# GD_Tcontroller_MCU.net
KiCad netlist of a schematic drawn in Altium Designer
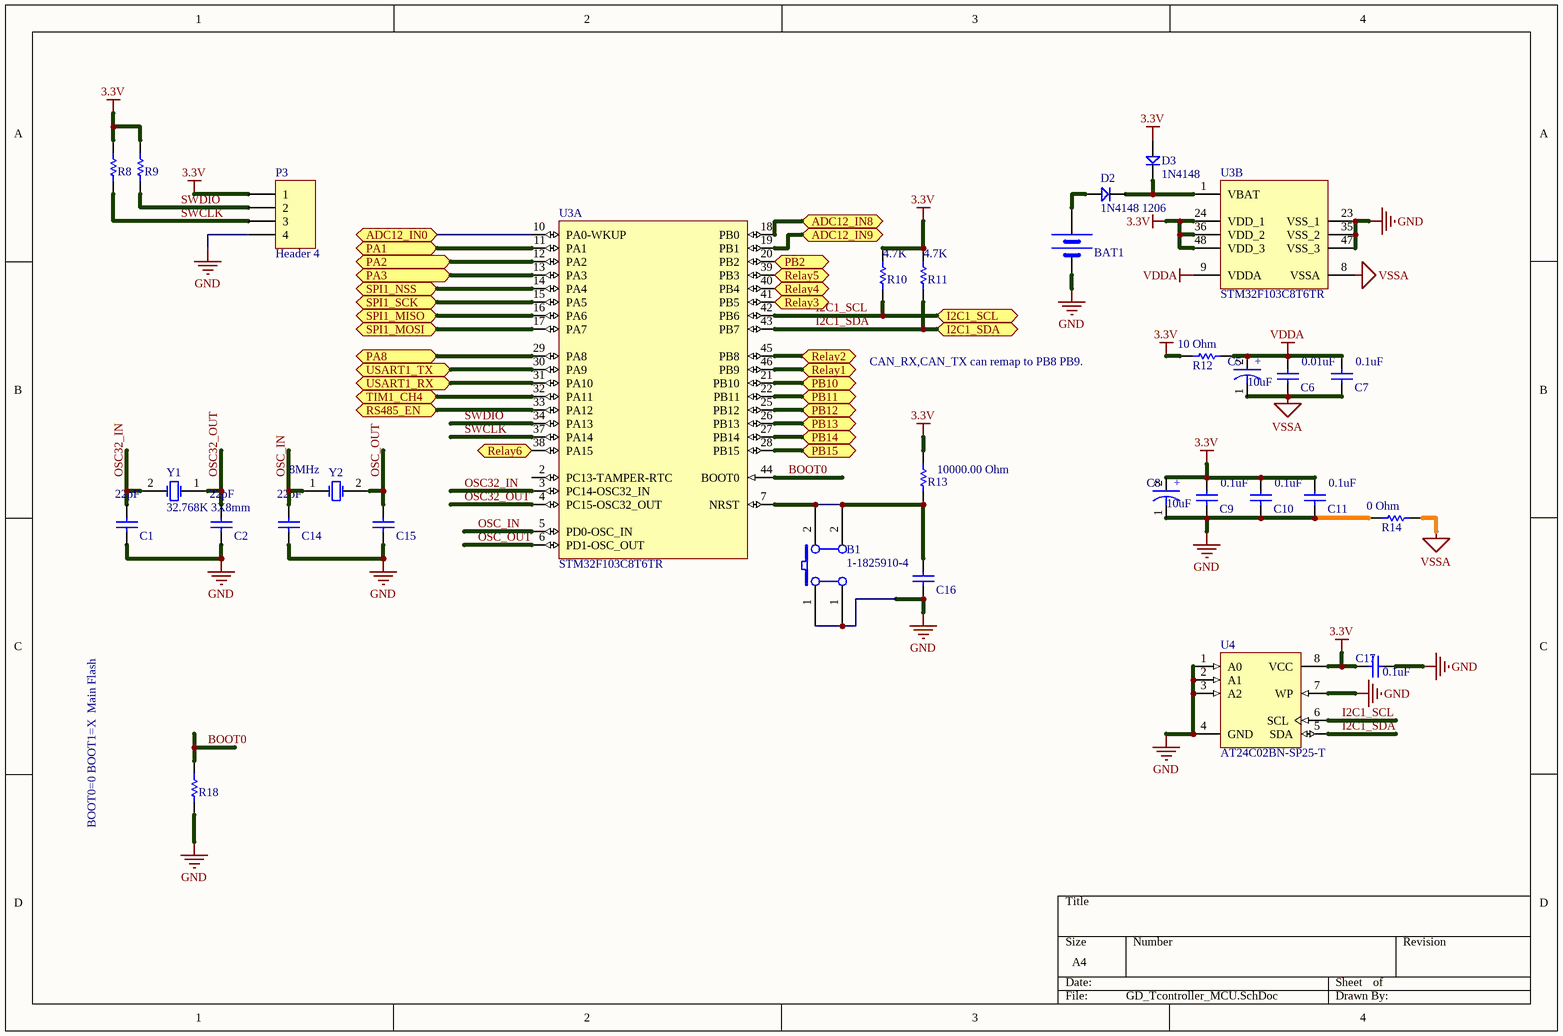
[diagram p0: GD_Tcontroller_MCU.SchDoc]

(export (version "E")
  (design (tool "Eeschema 10.0.6"))
  (components
    (comp (ref "B1")
      (value "1-1825910-4")
      (footprint "AN6_3P6_5")
      (description "Button ON/OFF，6.3X6.3X9.5MM,DIP-2")
      (fields (field (name "MANUFACTURER") "Tyco Electronics") (field (name "Comment") "SW PUSHBUTTON"))
      (libsource (lib "enlogic") (part "SW PUSHBUTTON"))
    )
    (comp (ref "BAT1")
      (value "CR1220 Sockect SMD")
      (footprint "BATM")
      (libsource (lib "战舰STM32开发板底板封装库") (part "BAT"))
    )
    (comp (ref "C1")
      (value "22pF")
      (footprint "C0805")
      (description "CAP 22pF 50V ±1% 0805 (2012 Metric) Thickness 0.75mm SMD")
      (fields (field (name "TOLERANCE") "±1%") (field (name "Comment") "CAP 22pF 50V 0805(2012)"))
      (libsource (lib "Altium Content Vault") (part "CMP-1036-01234-1"))
    )
    (comp (ref "C2")
      (value "22pF")
      (footprint "C0805")
      (description "CAP 22pF 50V ±1% 0805 (2012 Metric) Thickness 0.75mm SMD")
      (fields (field (name "TOLERANCE") "±1%") (field (name "Comment") "CAP 22pF 50V 0805(2012)"))
      (libsource (lib "Altium Content Vault") (part "CMP-1036-01234-1"))
    )
    (comp (ref "C5")
      (value "10uF")
      (footprint "TAN3216")
      (description "TAN 10uF 20% 10V 3216")
      (fields (field (name "MANUFACTURER") "AVX") (field (name "Comment") "CAPACITOR"))
      (libsource (lib "enlogic") (part "CAPACITOR"))
    )
    (comp (ref "C6")
      (value "0.01uF")
      (footprint "C0805")
      (description "CAP 0.1uF 50V ±20% 0805 (2012 Metric) Thickness 1mm SMD")
      (fields (field (name "TOLERANCE") "20%") (field (name "Comment") "CAP 0.01uF 50V 0805(2012)"))
      (libsource (lib "Altium Content Vault") (part "CMP-1036-00070-1"))
    )
    (comp (ref "C7")
      (value "0.1uF")
      (footprint "C0805")
      (description "CAP 0.1uF 50V ±20% 0805 (2012 Metric) Thickness 1mm SMD")
      (fields (field (name "TOLERANCE") "20%") (field (name "Comment") "CAP 0.1uF 50V 0805(2012)"))
      (libsource (lib "Altium Content Vault") (part "CMP-1036-00070-1"))
    )
    (comp (ref "C8")
      (value "10uF")
      (footprint "TAN3216")
      (description "TAN 10uF 20% 10V 3216")
      (fields (field (name "MANUFACTURER") "AVX") (field (name "Comment") "CAPACITOR"))
      (libsource (lib "enlogic") (part "CAPACITOR"))
    )
    (comp (ref "C9")
      (value "0.1uF")
      (footprint "C0805")
      (description "CAP 0.1uF 50V ±20% 0805 (2012 Metric) Thickness 1mm SMD")
      (fields (field (name "TOLERANCE") "20%") (field (name "Comment") "CAP 0.1uF 50V 0805(2012)"))
      (libsource (lib "Altium Content Vault") (part "CMP-1036-00070-1"))
    )
    (comp (ref "C10")
      (value "0.1uF")
      (footprint "C0805")
      (description "CAP 0.1uF 50V ±20% 0805 (2012 Metric) Thickness 1mm SMD")
      (fields (field (name "TOLERANCE") "20%") (field (name "Comment") "CAP 0.1uF 50V 0805(2012)"))
      (libsource (lib "Altium Content Vault") (part "CMP-1036-00070-1"))
    )
    (comp (ref "C11")
      (value "0.1uF")
      (footprint "C0805")
      (description "CAP 0.1uF 50V ±20% 0805 (2012 Metric) Thickness 1mm SMD")
      (fields (field (name "TOLERANCE") "20%") (field (name "Comment") "CAP 0.1uF 50V 0805(2012)"))
      (libsource (lib "Altium Content Vault") (part "CMP-1036-00070-1"))
    )
    (comp (ref "C14")
      (value "22pF")
      (footprint "C0805")
      (description "CAP 22pF 50V ±1% 0805 (2012 Metric) Thickness 0.75mm SMD")
      (fields (field (name "TOLERANCE") "±1%") (field (name "Comment") "CAP 22pF 50V 0805(2012)"))
      (libsource (lib "Altium Content Vault") (part "CMP-1036-01234-1"))
    )
    (comp (ref "C15")
      (value "CAP 22pF 50V 0805(2012)")
      (footprint "C0805")
      (description "CAP 22pF 50V ±1% 0805 (2012 Metric) Thickness 0.75mm SMD")
      (fields (field (name "TOLERANCE") "±1%"))
      (libsource (lib "Altium Content Vault") (part "CAP"))
    )
    (comp (ref "C16")
      (value "CAP 0.1uF 50V 0805(2012)")
      (footprint "C0805")
      (description "CAP 0.1uF 50V ±20% 0805 (2012 Metric) Thickness 1mm SMD")
      (fields (field (name "TOLERANCE") "20%"))
      (libsource (lib "Altium Content Vault") (part "CMP-1036-00070-1"))
    )
    (comp (ref "C17")
      (value "0.1uF")
      (footprint "C0805")
      (description "CAP 0.1uF 50V ±20% 0805 (2012 Metric) Thickness 1mm SMD")
      (fields (field (name "TOLERANCE") "20%") (field (name "Comment") "CAP 0.1uF 50V 0805(2012)"))
      (libsource (lib "Altium Content Vault") (part "CMP-1036-00070-1"))
    )
    (comp (ref "D2")
      (value "1N4148 1206")
      (footprint "DIODE_SOP")
      (description "1N4148")
      (libsource (lib "MiniSTM32 V3.0封装库") (part "D"))
    )
    (comp (ref "D3")
      (value "1N4148")
      (footprint "DIODE_SOP")
      (libsource (lib "MiniSTM32 V3.0封装库") (part "D"))
    )
    (comp (ref "P3")
      (value "Header 4")
      (footprint "HDR1X4")
      (description "Header, 4-Pin")
      (fields (field (name "PUBLISHER") "Altium Limited"))
      (libsource (lib "Miscellaneous Connectors") (part "Header 4"))
    )
    (comp (ref "R8")
      (value "10K 5% 0805(2012)")
      (footprint "R0805")
      (description "10K 0.125W 5% 0805 (2012 Metric)  SMD")
      (fields (field (name "POWER") "0.125 W") (field (name "TOLERANCE") "5 %"))
      (libsource (lib "Altium Content Vault") (part "RES"))
    )
    (comp (ref "R9")
      (value "10K 5% 0805(2012)")
      (footprint "R0805")
      (description "10K 0.125W 5% 0805 (2012 Metric)  SMD")
      (fields (field (name "POWER") "0.125 W") (field (name "TOLERANCE") "5 %"))
      (libsource (lib "Altium Content Vault") (part "RES"))
    )
    (comp (ref "R10")
      (value "4.7K")
      (footprint "R0805")
      (description "4.7K 0.125W 5% 0805 (2012 Metric)  SMD")
      (fields (field (name "POWER") "0.125 W") (field (name "TOLERANCE") "5 %"))
      (libsource (lib "Altium Content Vault") (part "CMP-1013-00098-1"))
    )
    (comp (ref "R11")
      (value "4.7K")
      (footprint "R0805")
      (description "4.7K 0.125W 5% 0805 (2012 Metric)  SMD")
      (fields (field (name "POWER") "0.125 W") (field (name "TOLERANCE") "5 %"))
      (libsource (lib "Altium Content Vault") (part "CMP-1013-00098-1"))
    )
    (comp (ref "R12")
      (value "10 Ohm")
      (footprint "R0805")
      (description "10Ohm 0.125W 5% 0805 (2012 Metric)  SMD")
      (fields (field (name "POWER") "0.125 W") (field (name "TOLERANCE") "5 %"))
      (libsource (lib "Altium Content Vault") (part "CMP-1013-00098-1"))
    )
    (comp (ref "R13")
      (value "10000.00 Ohm")
      (footprint "R0805")
      (description "10K 0.125W 5% 0805 (2012 Metric)  SMD")
      (fields (field (name "POWER") "0.125 W") (field (name "TOLERANCE") "5 %"))
      (libsource (lib "Altium Content Vault") (part "CMP-1013-00098-1"))
    )
    (comp (ref "R14")
      (value "0 Ohm")
      (footprint "R0805")
      (description "10Ohm 0.125W 5% 0805 (2012 Metric)  SMD")
      (fields (field (name "POWER") "0.125 W") (field (name "TOLERANCE") "5 %"))
      (libsource (lib "Altium Content Vault") (part "CMP-1013-00098-1"))
    )
    (comp (ref "R18")
      (value "10K 5% 0805(2012)")
      (footprint "R0805")
      (description "10K 0.125W 5% 0805 (2012 Metric)  SMD")
      (fields (field (name "POWER") "0.125 W") (field (name "TOLERANCE") "5 %"))
      (libsource (lib "Altium Content Vault") (part "RES"))
    )
    (comp (ref "U3")
      (value "STM32F103C8T6TR")
      (footprint "STM-LQFP48_L")
      (libsource (lib "Altium Content Vault") (part "CMP-0237-00216-3"))
    )
    (comp (ref "U4")
      (value "AT24C02BN-SP25-T")
      (footprint "8S1_L")
      (libsource (lib "Altium Content Vault") (part "CMP-0152-00023-1"))
    )
    (comp (ref "Y1")
      (value "32.768K 3X8mm")
      (footprint "XTAL32")
      (description "32.768K 3mmX8mm")
      (fields (field (name "PUBLISHER") "Altium Limited"))
      (libsource (lib "战舰STM32开发板底板封装库") (part "XTAL_1"))
    )
    (comp (ref "Y2")
      (value "8MHz")
      (footprint "XTAL_US")
      (description "Crystal Oscillator")
      (fields (field (name "PUBLISHER") "Altium Limited"))
      (libsource (lib "战舰STM32开发板底板封装库") (part "XTAL"))
    )
  )
  (nets
    (net (code "1") (name "/ADC12_IN0") (class "Default")
      (node (ref "U3") (pin "10") (pinfunction "PA0-WKUP_10") (pintype "bidirectional"))
    )
    (net (code "2") (name "/ADC12_IN8") (class "Default")
      (node (ref "U3") (pin "18") (pinfunction "PB0_18") (pintype "bidirectional"))
    )
    (net (code "3") (name "/ADC12_IN9") (class "Default")
      (node (ref "U3") (pin "19") (pinfunction "PB1_19") (pintype "bidirectional"))
    )
    (net (code "4") (name "/BOOT0") (class "Default")
      (node (ref "R18") (pin "1") (pinfunction "1_1") (pintype "passive"))
      (node (ref "U3") (pin "44") (pinfunction "BOOT0_44") (pintype "input"))
    )
    (net (code "5") (name "/I2C1_SCL") (class "Default")
      (node (ref "R10") (pin "2") (pinfunction "2_2") (pintype "passive"))
      (node (ref "U3") (pin "42") (pinfunction "PB6_42") (pintype "bidirectional"))
      (node (ref "U4") (pin "6") (pinfunction "SCL_6") (pintype "input"))
    )
    (net (code "6") (name "/I2C1_SDA") (class "Default")
      (node (ref "R11") (pin "2") (pinfunction "2_2") (pintype "passive"))
      (node (ref "U3") (pin "43") (pinfunction "PB7_43") (pintype "bidirectional"))
      (node (ref "U4") (pin "5") (pinfunction "SDA_5") (pintype "bidirectional"))
    )
    (net (code "7") (name "/OSC32_IN") (class "Default")
      (node (ref "C1") (pin "2") (pinfunction "2_2") (pintype "passive"))
      (node (ref "U3") (pin "3") (pinfunction "PC14-OSC32_IN_3") (pintype "bidirectional"))
      (node (ref "Y1") (pin "2") (pinfunction "OSC2_2") (pintype "passive"))
    )
    (net (code "8") (name "/OSC32_OUT") (class "Default")
      (node (ref "C2") (pin "2") (pinfunction "2_2") (pintype "passive"))
      (node (ref "U3") (pin "4") (pinfunction "PC15-OSC32_OUT_4") (pintype "bidirectional"))
      (node (ref "Y1") (pin "1") (pinfunction "OSC1_1") (pintype "passive"))
    )
    (net (code "9") (name "/OSC_IN") (class "Default")
      (node (ref "C14") (pin "2") (pinfunction "2_2") (pintype "passive"))
      (node (ref "U3") (pin "5") (pinfunction "PD0-OSC_IN_5") (pintype "bidirectional"))
      (node (ref "Y2") (pin "1") (pinfunction "OSC1_1") (pintype "passive"))
    )
    (net (code "10") (name "/OSC_OUT") (class "Default")
      (node (ref "C15") (pin "2") (pinfunction "2_2") (pintype "passive"))
      (node (ref "U3") (pin "6") (pinfunction "PD1-OSC_OUT_6") (pintype "bidirectional"))
      (node (ref "Y2") (pin "2") (pinfunction "OSC2_2") (pintype "passive"))
    )
    (net (code "11") (name "/PA1") (class "Default")
      (node (ref "U3") (pin "11") (pinfunction "PA1_11") (pintype "bidirectional"))
    )
    (net (code "12") (name "/PA2") (class "Default")
      (node (ref "U3") (pin "12") (pinfunction "PA2_12") (pintype "bidirectional"))
    )
    (net (code "13") (name "/PA3") (class "Default")
      (node (ref "U3") (pin "13") (pinfunction "PA3_13") (pintype "bidirectional"))
    )
    (net (code "14") (name "/PA8") (class "Default")
      (node (ref "U3") (pin "29") (pinfunction "PA8_29") (pintype "bidirectional"))
    )
    (net (code "15") (name "/PB2") (class "Default")
      (node (ref "U3") (pin "20") (pinfunction "PB2_20") (pintype "bidirectional"))
    )
    (net (code "16") (name "/PB10") (class "Default")
      (node (ref "U3") (pin "21") (pinfunction "PB10_21") (pintype "bidirectional"))
    )
    (net (code "17") (name "/PB11") (class "Default")
      (node (ref "U3") (pin "22") (pinfunction "PB11_22") (pintype "bidirectional"))
    )
    (net (code "18") (name "/PB12") (class "Default")
      (node (ref "U3") (pin "25") (pinfunction "PB12_25") (pintype "bidirectional"))
    )
    (net (code "19") (name "/PB13") (class "Default")
      (node (ref "U3") (pin "26") (pinfunction "PB13_26") (pintype "bidirectional"))
    )
    (net (code "20") (name "/PB14") (class "Default")
      (node (ref "U3") (pin "27") (pinfunction "PB14_27") (pintype "bidirectional"))
    )
    (net (code "21") (name "/PB15") (class "Default")
      (node (ref "U3") (pin "28") (pinfunction "PB15_28") (pintype "bidirectional"))
    )
    (net (code "22") (name "/RS485_EN") (class "Default")
      (node (ref "U3") (pin "33") (pinfunction "PA12_33") (pintype "bidirectional"))
    )
    (net (code "23") (name "/Relay1") (class "Default")
      (node (ref "U3") (pin "46") (pinfunction "PB9_46") (pintype "bidirectional"))
    )
    (net (code "24") (name "/Relay2") (class "Default")
      (node (ref "U3") (pin "45") (pinfunction "PB8_45") (pintype "bidirectional"))
    )
    (net (code "25") (name "/Relay3") (class "Default")
      (node (ref "U3") (pin "41") (pinfunction "PB5_41") (pintype "bidirectional"))
    )
    (net (code "26") (name "/Relay4") (class "Default")
      (node (ref "U3") (pin "40") (pinfunction "PB4_40") (pintype "bidirectional"))
    )
    (net (code "27") (name "/Relay5") (class "Default")
      (node (ref "U3") (pin "39") (pinfunction "PB3_39") (pintype "bidirectional"))
    )
    (net (code "28") (name "/Relay6") (class "Default")
      (node (ref "U3") (pin "38") (pinfunction "PA15_38") (pintype "bidirectional"))
    )
    (net (code "29") (name "/SPI1_MISO") (class "Default")
      (node (ref "U3") (pin "16") (pinfunction "PA6_16") (pintype "bidirectional"))
    )
    (net (code "30") (name "/SPI1_MOSI") (class "Default")
      (node (ref "U3") (pin "17") (pinfunction "PA7_17") (pintype "bidirectional"))
    )
    (net (code "31") (name "/SPI1_NSS") (class "Default")
      (node (ref "U3") (pin "14") (pinfunction "PA4_14") (pintype "bidirectional"))
    )
    (net (code "32") (name "/SPI1_SCK") (class "Default")
      (node (ref "U3") (pin "15") (pinfunction "PA5_15") (pintype "bidirectional"))
    )
    (net (code "33") (name "/SWCLK") (class "Default")
      (node (ref "P3") (pin "3") (pinfunction "3_3") (pintype "passive"))
      (node (ref "R8") (pin "2") (pinfunction "2_2") (pintype "passive"))
      (node (ref "U3") (pin "37") (pinfunction "PA14_37") (pintype "bidirectional"))
    )
    (net (code "34") (name "/SWDIO") (class "Default")
      (node (ref "P3") (pin "2") (pinfunction "2_2") (pintype "passive"))
      (node (ref "R9") (pin "2") (pinfunction "2_2") (pintype "passive"))
      (node (ref "U3") (pin "34") (pinfunction "PA13_34") (pintype "bidirectional"))
    )
    (net (code "35") (name "/TIM1_CH4") (class "Default")
      (node (ref "U3") (pin "32") (pinfunction "PA11_32") (pintype "bidirectional"))
    )
    (net (code "36") (name "/USART1_RX") (class "Default")
      (node (ref "U3") (pin "31") (pinfunction "PA10_31") (pintype "bidirectional"))
    )
    (net (code "37") (name "/USART1_TX") (class "Default")
      (node (ref "U3") (pin "30") (pinfunction "PA9_30") (pintype "bidirectional"))
    )
    (net (code "38") (name "3.3V") (class "Default")
      (node (ref "C10") (pin "2") (pinfunction "2_2") (pintype "passive"))
      (node (ref "C11") (pin "2") (pinfunction "2_2") (pintype "passive"))
      (node (ref "C17") (pin "2") (pinfunction "2_2") (pintype "passive"))
      (node (ref "C8") (pin "2") (pinfunction "2_2") (pintype "passive"))
      (node (ref "C9") (pin "2") (pinfunction "2_2") (pintype "passive"))
      (node (ref "D3") (pin "1") (pintype "passive"))
      (node (ref "P3") (pin "1") (pinfunction "1_1") (pintype "passive"))
      (node (ref "R10") (pin "1") (pinfunction "1_1") (pintype "passive"))
      (node (ref "R11") (pin "1") (pinfunction "1_1") (pintype "passive"))
      (node (ref "R12") (pin "1") (pinfunction "1_1") (pintype "passive"))
      (node (ref "R13") (pin "1") (pinfunction "1_1") (pintype "passive"))
      (node (ref "R8") (pin "1") (pinfunction "1_1") (pintype "passive"))
      (node (ref "R9") (pin "1") (pinfunction "1_1") (pintype "passive"))
      (node (ref "U3") (pin "24") (pinfunction "VDD_1_24") (pintype "power_in"))
      (node (ref "U3") (pin "36") (pinfunction "VDD_2_36") (pintype "power_in"))
      (node (ref "U3") (pin "48") (pinfunction "VDD_3_48") (pintype "power_in"))
      (node (ref "U4") (pin "8") (pinfunction "VCC_8") (pintype "power_in"))
    )
    (net (code "39") (name "GND") (class "Default")
      (node (ref "B1") (pin "1") (pinfunction "A0_1") (pintype "passive"))
      (node (ref "BAT1") (pin "2") (pinfunction "GND_2") (pintype "passive"))
      (node (ref "C1") (pin "1") (pinfunction "1_1") (pintype "passive"))
      (node (ref "C10") (pin "1") (pinfunction "1_1") (pintype "passive"))
      (node (ref "C11") (pin "1") (pinfunction "1_1") (pintype "passive"))
      (node (ref "C14") (pin "1") (pinfunction "1_1") (pintype "passive"))
      (node (ref "C15") (pin "1") (pinfunction "1_1") (pintype "passive"))
      (node (ref "C16") (pin "1") (pinfunction "1_1") (pintype "passive"))
      (node (ref "C17") (pin "1") (pinfunction "1_1") (pintype "passive"))
      (node (ref "C2") (pin "1") (pinfunction "1_1") (pintype "passive"))
      (node (ref "C8") (pin "1") (pinfunction "1_1") (pintype "passive"))
      (node (ref "C9") (pin "1") (pinfunction "1_1") (pintype "passive"))
      (node (ref "P3") (pin "4") (pinfunction "4_4") (pintype "passive"))
      (node (ref "R14") (pin "1") (pinfunction "1_1") (pintype "passive"))
      (node (ref "R18") (pin "2") (pinfunction "2_2") (pintype "passive"))
      (node (ref "U3") (pin "23") (pinfunction "VSS_1_23") (pintype "power_in"))
      (node (ref "U3") (pin "35") (pinfunction "VSS_2_35") (pintype "power_in"))
      (node (ref "U3") (pin "47") (pinfunction "VSS_3_47") (pintype "power_in"))
      (node (ref "U4") (pin "1") (pinfunction "A0_1") (pintype "input"))
      (node (ref "U4") (pin "2") (pinfunction "A1_2") (pintype "input"))
      (node (ref "U4") (pin "3") (pinfunction "A2_3") (pintype "input"))
      (node (ref "U4") (pin "4") (pinfunction "GND_4") (pintype "power_in"))
      (node (ref "U4") (pin "7") (pinfunction "WP_7") (pintype "input"))
    )
    (net (code "40") (name "Net-(B1-B0)") (class "Default")
      (node (ref "B1") (pin "2") (pinfunction "B0_2") (pintype "passive"))
      (node (ref "C16") (pin "2") (pinfunction "2_2") (pintype "passive"))
      (node (ref "R13") (pin "2") (pinfunction "2_2") (pintype "passive"))
      (node (ref "U3") (pin "7") (pinfunction "NRST_7") (pintype "bidirectional"))
    )
    (net (code "41") (name "Net-(BAT1-VCC)") (class "Default")
      (node (ref "BAT1") (pin "1") (pinfunction "VCC_1") (pintype "passive"))
      (node (ref "D2") (pin "1") (pintype "passive"))
    )
    (net (code "42") (name "Net-(U3B-VBAT)") (class "Default")
      (node (ref "D2") (pin "2") (pintype "passive"))
      (node (ref "D3") (pin "2") (pintype "passive"))
      (node (ref "U3") (pin "1") (pinfunction "VBAT_1") (pintype "power_in"))
    )
    (net (code "43") (name "VDDA") (class "Default")
      (node (ref "C5") (pin "2") (pinfunction "2_2") (pintype "passive"))
      (node (ref "C6") (pin "2") (pinfunction "2_2") (pintype "passive"))
      (node (ref "C7") (pin "2") (pinfunction "2_2") (pintype "passive"))
      (node (ref "R12") (pin "2") (pinfunction "2_2") (pintype "passive"))
      (node (ref "U3") (pin "9") (pinfunction "VDDA_9") (pintype "power_in"))
    )
    (net (code "44") (name "VSSA") (class "Default")
      (node (ref "C5") (pin "1") (pinfunction "1_1") (pintype "passive"))
      (node (ref "C6") (pin "1") (pinfunction "1_1") (pintype "passive"))
      (node (ref "C7") (pin "1") (pinfunction "1_1") (pintype "passive"))
      (node (ref "R14") (pin "2") (pinfunction "2_2") (pintype "passive"))
      (node (ref "U3") (pin "8") (pinfunction "VSSA_8") (pintype "power_in"))
    )
    (net (code "45") (name "unconnected-(U3A-PC13-TAMPER-RTC-Pad2)") (class "Default")
      (node (ref "U3") (pin "2") (pinfunction "PC13-TAMPER-RTC_2") (pintype "bidirectional"))
    )
  )
)
